# I2C_DP_Sensor_2.net
KiCad netlist of a schematic drawn in Altium Designer
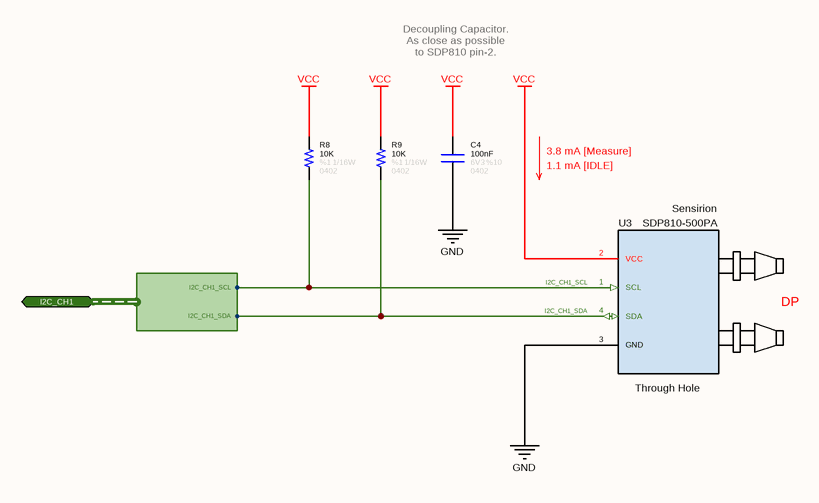
[diagram p0: I2C DP Sensor 2.SchDoc]

(export (version "E")
  (design (tool "Eeschema 10.0.6"))
  (components
    (comp (ref "C4")
      (value "100nF")
      (footprint "CAPACITOR_0402")
      (description "Capacitor - 100nF [0402-6V3] (Ceramic)")
      (fields
        (field (name "MANUFACTURER PART NUMBER") "04026D104KAT4A")
        (field (name "TOLERANCE") "%10")
        (field (name "VOLTAGE") "6V3")
        (field (name "CASE") "0402")
        (field (name "Comment") "Capacitor - 100nF [0402] (Ceramic)")
      )
      (libsource (lib "P101DA_Library") (part "Capacitor - 100nF [0402-6V3]"))
    )
    (comp (ref "R8")
      (value "10K")
      (footprint "RESISTOR_0402")
      (description "Thick Film Resistors - SMD 1/16 W 10 KOhm 1%")
      (fields
        (field (name "MANUFACTURER PART NUMBER") "CRCW040210K0FKED")
        (field (name "TOLERANCE") "%1")
        (field (name "CASE") "0402")
        (field (name "POWER") "1/16W")
        (field (name "Comment") "10K - 0402 - %1 - 1/16W")
      )
      (libsource (lib "P101DA_Library") (part "Resistor - 10K [0402]"))
    )
    (comp (ref "R9")
      (value "10K")
      (footprint "RESISTOR_0402")
      (description "Thick Film Resistors - SMD 1/16 W 10 KOhm 1%")
      (fields
        (field (name "MANUFACTURER PART NUMBER") "CRCW040210K0FKED")
        (field (name "TOLERANCE") "%1")
        (field (name "CASE") "0402")
        (field (name "POWER") "1/16W")
        (field (name "Comment") "10K - 0402 - %1 - 1/16W")
      )
      (libsource (lib "P101DA_Library") (part "Resistor - 10K [0402]"))
    )
    (comp (ref "U3")
      (value "SDP810-500PA")
      (footprint "SDP810-500PA")
      (description "Board Mount Pressure Sensors Tube Connection, I2C , 500Pa")
      (fields
        (field (name "MANUFACTURER NAME") "Sensirion")
        (field (name "MANUFACTURER PART NUMBER") "SDP810-500PA")
        (field (name "CASE") "Through Hole")
      )
      (libsource (lib "P101DA_Library") (part "IC - SDP810-500PA"))
    )
  )
  (nets
    (net (code "2") (name "/I2C_CH1_SCL") (class "Default")
      (node (ref "R8") (pin "1") (pinfunction "1_1") (pintype "passive"))
      (node (ref "U3") (pin "1") (pinfunction "SCL_1") (pintype "input"))
    )
    (net (code "3") (name "/I2C_CH1_SDA") (class "Default")
      (node (ref "R9") (pin "1") (pinfunction "1_1") (pintype "passive"))
      (node (ref "U3") (pin "4") (pinfunction "SDA_4") (pintype "bidirectional"))
    )
    (net (code "5") (name "GND") (class "Default")
      (node (ref "C4") (pin "1") (pinfunction "1_1") (pintype "passive"))
      (node (ref "U3") (pin "3") (pinfunction "GND_3") (pintype "passive"))
    )
    (net (code "6") (name "VCC") (class "Default")
      (node (ref "C4") (pin "2") (pinfunction "2_2") (pintype "passive"))
      (node (ref "R8") (pin "2") (pinfunction "2_2") (pintype "passive"))
      (node (ref "R9") (pin "2") (pinfunction "2_2") (pintype "passive"))
      (node (ref "U3") (pin "2") (pinfunction "VCC_2") (pintype "power_in"))
    )
  )
)
